# Sheet1.net
KiCad netlist of a schematic drawn in Altium Designer
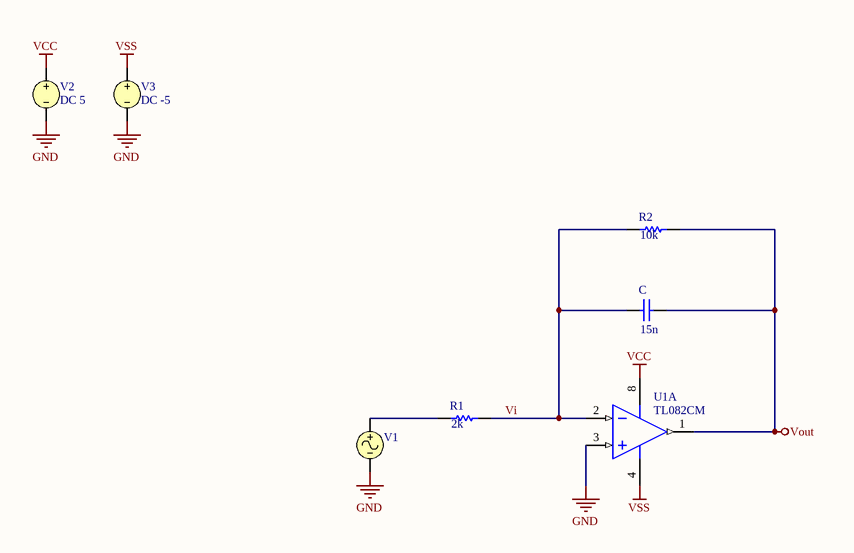
[diagram p0: Sheet1.SchDoc]

(export (version "E")
  (design (tool "Eeschema 10.0.6"))
  (components
    (comp (ref "C")
      (value "15n")
      (footprint "RAD-0.3")
      (description "Capacitor")
      (fields (field (name "Comment") "Cap") (field (name "PUBLISHER") "Altium Limited"))
      (libsource (lib "Miscellaneous Devices") (part "Cap"))
    )
    (comp (ref "R1")
      (value "2k")
      (footprint "AXIAL-0.3")
      (description "Resistor")
      (fields (field (name "Comment") "Res1") (field (name "PUBLISHER") "Altium Limited"))
      (libsource (lib "Miscellaneous Devices") (part "Res1"))
    )
    (comp (ref "R2")
      (value "10k")
      (footprint "AXIAL-0.3")
      (description "Resistor")
      (fields (field (name "Comment") "Res1") (field (name "PUBLISHER") "Altium Limited"))
      (libsource (lib "Miscellaneous Devices") (part "Res1"))
    )
    (comp (ref "U1")
      (value "TL082CM")
      (footprint "M08A_N")
      (description "Wide Bandwidth Dual JFET Input Operational Amplifier, 8-pin Narrow SOIC")
      (fields
        (field (name "MANUFACTURER") "National Semiconductor")
        (field (name "PUBLISHER") "Altium Limited")
      )
      (libsource (lib "NSC Amplifier") (part "TL082CM"))
    )
    (comp (ref "V1")
      (value "PULSE(-1 1 0 1n 1n 0.05 0.1 0)")
      (description "Sinusoidal Voltage Source")
      (fields (field (name "PUBLISHER") "Altium Limited"))
      (libsource (lib "Simulation Sources") (part "VSIN"))
    )
    (comp (ref "V2")
      (value "DC 5")
      (description "Voltage Source")
      (fields (field (name "PUBLISHER") "Altium Limited"))
      (libsource (lib "Simulation Sources") (part "VSRC"))
    )
    (comp (ref "V3")
      (value "DC -5")
      (description "Voltage Source")
      (fields (field (name "PUBLISHER") "Altium Limited"))
      (libsource (lib "Simulation Sources") (part "VSRC"))
    )
  )
  (nets
    (net (code "2") (name "/Vi") (class "Default")
      (node (ref "C") (pin "1") (pinfunction "1_1") (pintype "passive"))
      (node (ref "R1") (pin "2") (pinfunction "2_2") (pintype "passive"))
      (node (ref "R2") (pin "1") (pinfunction "1_1") (pintype "passive"))
      (node (ref "U1") (pin "2") (pinfunction "INA-_2") (pintype "input"))
    )
    (net (code "3") (name "GND") (class "Default")
      (node (ref "U1") (pin "3") (pinfunction "INA+_3") (pintype "input"))
      (node (ref "V1") (pin "2") (pinfunction "2_2") (pintype "passive"))
      (node (ref "V2") (pin "2") (pinfunction "2_2") (pintype "passive"))
      (node (ref "V3") (pin "2") (pinfunction "2_2") (pintype "passive"))
    )
    (net (code "4") (name "Net-(R1-Pad1)") (class "Default")
      (node (ref "R1") (pin "1") (pinfunction "1_1") (pintype "passive"))
      (node (ref "V1") (pin "1") (pinfunction "1_1") (pintype "passive"))
    )
    (net (code "5") (name "VCC") (class "Default")
      (node (ref "U1") (pin "8") (pinfunction "V+_8") (pintype "power_in"))
      (node (ref "V2") (pin "1") (pinfunction "1_1") (pintype "passive"))
    )
    (net (code "6") (name "VSS") (class "Default")
      (node (ref "U1") (pin "4") (pinfunction "V-_4") (pintype "power_in"))
      (node (ref "V3") (pin "1") (pinfunction "1_1") (pintype "passive"))
    )
    (net (code "7") (name "Vout") (class "Default")
      (node (ref "C") (pin "2") (pinfunction "2_2") (pintype "passive"))
      (node (ref "R2") (pin "2") (pinfunction "2_2") (pintype "passive"))
      (node (ref "U1") (pin "1") (pinfunction "OUTA_1") (pintype "output"))
    )
  )
)
